# RightBar1_SchDoc.net
KiCad netlist of a schematic drawn in Altium Designer
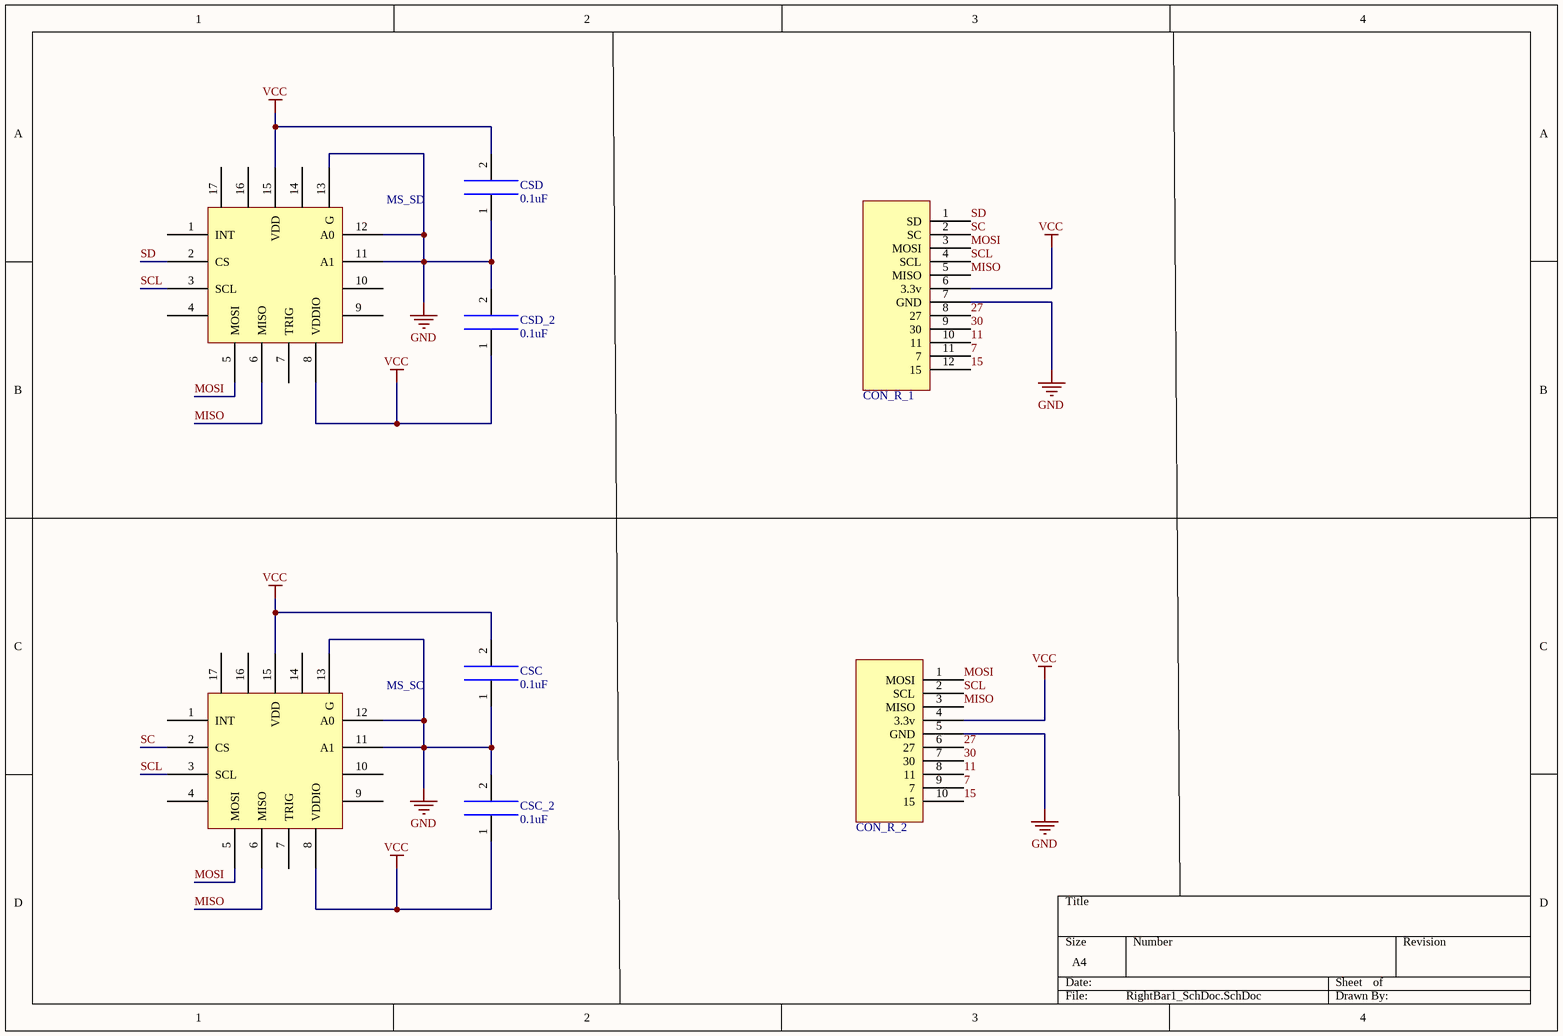
[diagram p0: RightBar1_SchDoc.SchDoc]

(export (version "E")
  (design (tool "Eeschema 10.0.6"))
  (components
    (comp (ref "CON_R_1")
      (value "PIN_right")
      (footprint "PIN_RIGHT_1")
      (libsource (lib "MagWaySchlib") (part "PIN_right"))
    )
    (comp (ref "CON_R_2")
      (value "PIN_right")
      (footprint "PIN_RIGHT_2")
      (libsource (lib "MagWaySchlib") (part "PIN_right_2"))
    )
    (comp (ref "CSC")
      (value "0.1uF")
      (footprint "CAP_0603")
      (description "Capacitance")
      (libsource (lib "MagWaySchlib") (part "CAP"))
    )
    (comp (ref "CSC_2")
      (value "0.1uF")
      (footprint "CAP_0603")
      (description "Capacitance")
      (libsource (lib "MagWaySchlib") (part "CAP"))
    )
    (comp (ref "CSD")
      (value "0.1uF")
      (footprint "CAP_0603")
      (description "Capacitance")
      (libsource (lib "MagWaySchlib") (part "CAP"))
    )
    (comp (ref "CSD_2")
      (value "0.1uF")
      (footprint "CAP_0603")
      (description "Capacitance")
      (libsource (lib "MagWaySchlib") (part "CAP"))
    )
    (comp (ref "MS_SC")
      (value "MLX90393SLW ABA 011 RE")
      (footprint "MLX90393")
      (description "MLX90393 Sensor")
      (libsource (lib "MagWaySchlib") (part "MLX90393SLW ABA 011 RE"))
    )
    (comp (ref "MS_SD")
      (value "MLX90393SLW ABA 011 RE")
      (footprint "MLX90393")
      (description "MLX90393 Sensor")
      (libsource (lib "MagWaySchlib") (part "MLX90393SLW ABA 011 RE"))
    )
  )
  (nets
    (net (code "1") (name "/7") (class "Default")
      (node (ref "CON_R_1") (pin "11") (pinfunction "7_11") (pintype "passive"))
      (node (ref "CON_R_2") (pin "9") (pinfunction "7_9") (pintype "passive"))
    )
    (net (code "2") (name "/11") (class "Default")
      (node (ref "CON_R_1") (pin "10") (pinfunction "11_10") (pintype "passive"))
      (node (ref "CON_R_2") (pin "8") (pinfunction "11_8") (pintype "passive"))
    )
    (net (code "3") (name "/15") (class "Default")
      (node (ref "CON_R_1") (pin "12") (pinfunction "15_12") (pintype "passive"))
      (node (ref "CON_R_2") (pin "10") (pinfunction "15_10") (pintype "passive"))
    )
    (net (code "4") (name "/27") (class "Default")
      (node (ref "CON_R_1") (pin "8") (pinfunction "27_8") (pintype "passive"))
      (node (ref "CON_R_2") (pin "6") (pinfunction "27_6") (pintype "passive"))
    )
    (net (code "5") (name "/30") (class "Default")
      (node (ref "CON_R_1") (pin "9") (pinfunction "30_9") (pintype "passive"))
      (node (ref "CON_R_2") (pin "7") (pinfunction "30_7") (pintype "passive"))
    )
    (net (code "6") (name "/MISO") (class "Default")
      (node (ref "CON_R_1") (pin "5") (pinfunction "MISO_5") (pintype "passive"))
      (node (ref "CON_R_2") (pin "3") (pinfunction "MISO_3") (pintype "passive"))
      (node (ref "MS_SC") (pin "6") (pinfunction "MISO_6") (pintype "passive"))
      (node (ref "MS_SD") (pin "6") (pinfunction "MISO_6") (pintype "passive"))
    )
    (net (code "7") (name "/MOSI") (class "Default")
      (node (ref "CON_R_1") (pin "3") (pinfunction "MOSI_3") (pintype "passive"))
      (node (ref "CON_R_2") (pin "1") (pinfunction "MOSI_1") (pintype "passive"))
      (node (ref "MS_SC") (pin "5") (pinfunction "MOSI_5") (pintype "passive"))
      (node (ref "MS_SD") (pin "5") (pinfunction "MOSI_5") (pintype "passive"))
    )
    (net (code "8") (name "/SC") (class "Default")
      (node (ref "CON_R_1") (pin "2") (pinfunction "SC_2") (pintype "passive"))
      (node (ref "MS_SC") (pin "2") (pinfunction "CS_2") (pintype "passive"))
    )
    (net (code "9") (name "/SCL") (class "Default")
      (node (ref "CON_R_1") (pin "4") (pinfunction "SCL_4") (pintype "passive"))
      (node (ref "CON_R_2") (pin "2") (pinfunction "SCL_2") (pintype "passive"))
      (node (ref "MS_SC") (pin "3") (pinfunction "SCL_3") (pintype "passive"))
      (node (ref "MS_SD") (pin "3") (pinfunction "SCL_3") (pintype "passive"))
    )
    (net (code "10") (name "/SD") (class "Default")
      (node (ref "CON_R_1") (pin "1") (pinfunction "SD_1") (pintype "passive"))
      (node (ref "MS_SD") (pin "2") (pinfunction "CS_2") (pintype "passive"))
    )
    (net (code "11") (name "GND") (class "Default")
      (node (ref "CON_R_1") (pin "7") (pinfunction "GND_7") (pintype "passive"))
      (node (ref "CON_R_2") (pin "5") (pinfunction "GND_5") (pintype "passive"))
      (node (ref "CSC") (pin "1") (pintype "passive"))
      (node (ref "CSC_2") (pin "2") (pintype "passive"))
      (node (ref "CSD") (pin "1") (pintype "passive"))
      (node (ref "CSD_2") (pin "2") (pintype "passive"))
      (node (ref "MS_SC") (pin "11") (pinfunction "A1_11") (pintype "passive"))
      (node (ref "MS_SC") (pin "12") (pinfunction "A0_12") (pintype "passive"))
      (node (ref "MS_SC") (pin "13") (pinfunction "G_13") (pintype "passive"))
      (node (ref "MS_SD") (pin "11") (pinfunction "A1_11") (pintype "passive"))
      (node (ref "MS_SD") (pin "12") (pinfunction "A0_12") (pintype "passive"))
      (node (ref "MS_SD") (pin "13") (pinfunction "G_13") (pintype "passive"))
    )
    (net (code "12") (name "VCC") (class "Default")
      (node (ref "CON_R_1") (pin "6") (pinfunction "3.3v_6") (pintype "passive"))
      (node (ref "CON_R_2") (pin "4") (pinfunction "3.3v_4") (pintype "passive"))
      (node (ref "CSC") (pin "2") (pintype "passive"))
      (node (ref "CSC_2") (pin "1") (pintype "passive"))
      (node (ref "CSD") (pin "2") (pintype "passive"))
      (node (ref "CSD_2") (pin "1") (pintype "passive"))
      (node (ref "MS_SC") (pin "15") (pinfunction "VDD_15") (pintype "passive"))
      (node (ref "MS_SC") (pin "8") (pinfunction "VDDIO_8") (pintype "passive"))
      (node (ref "MS_SD") (pin "15") (pinfunction "VDD_15") (pintype "passive"))
      (node (ref "MS_SD") (pin "8") (pinfunction "VDDIO_8") (pintype "passive"))
    )
    (net (code "13") (name "unconnected-(MS_SC-INT-Pad1)") (class "Default")
      (node (ref "MS_SC") (pin "1") (pinfunction "INT_1") (pintype "passive"))
    )
    (net (code "14") (name "unconnected-(MS_SC-Pad4)") (class "Default")
      (node (ref "MS_SC") (pin "4") (pintype "passive"))
    )
    (net (code "15") (name "unconnected-(MS_SC-Pad9)") (class "Default")
      (node (ref "MS_SC") (pin "9") (pintype "passive"))
    )
    (net (code "16") (name "unconnected-(MS_SC-Pad10)") (class "Default")
      (node (ref "MS_SC") (pin "10") (pintype "passive"))
    )
    (net (code "17") (name "unconnected-(MS_SC-Pad14)") (class "Default")
      (node (ref "MS_SC") (pin "14") (pintype "passive"))
    )
    (net (code "18") (name "unconnected-(MS_SC-Pad16)") (class "Default")
      (node (ref "MS_SC") (pin "16") (pintype "passive"))
    )
    (net (code "19") (name "unconnected-(MS_SC-Pad17)") (class "Default")
      (node (ref "MS_SC") (pin "17") (pintype "passive"))
    )
    (net (code "20") (name "unconnected-(MS_SC-TRIG-Pad7)") (class "Default")
      (node (ref "MS_SC") (pin "7") (pinfunction "TRIG_7") (pintype "passive"))
    )
    (net (code "21") (name "unconnected-(MS_SD-INT-Pad1)") (class "Default")
      (node (ref "MS_SD") (pin "1") (pinfunction "INT_1") (pintype "passive"))
    )
    (net (code "22") (name "unconnected-(MS_SD-Pad4)") (class "Default")
      (node (ref "MS_SD") (pin "4") (pintype "passive"))
    )
    (net (code "23") (name "unconnected-(MS_SD-Pad9)") (class "Default")
      (node (ref "MS_SD") (pin "9") (pintype "passive"))
    )
    (net (code "24") (name "unconnected-(MS_SD-Pad10)") (class "Default")
      (node (ref "MS_SD") (pin "10") (pintype "passive"))
    )
    (net (code "25") (name "unconnected-(MS_SD-Pad14)") (class "Default")
      (node (ref "MS_SD") (pin "14") (pintype "passive"))
    )
    (net (code "26") (name "unconnected-(MS_SD-Pad16)") (class "Default")
      (node (ref "MS_SD") (pin "16") (pintype "passive"))
    )
    (net (code "27") (name "unconnected-(MS_SD-Pad17)") (class "Default")
      (node (ref "MS_SD") (pin "17") (pintype "passive"))
    )
    (net (code "28") (name "unconnected-(MS_SD-TRIG-Pad7)") (class "Default")
      (node (ref "MS_SD") (pin "7") (pinfunction "TRIG_7") (pintype "passive"))
    )
  )
)
